# Operant-Front.net
KiCad netlist of a schematic drawn in EAGLE
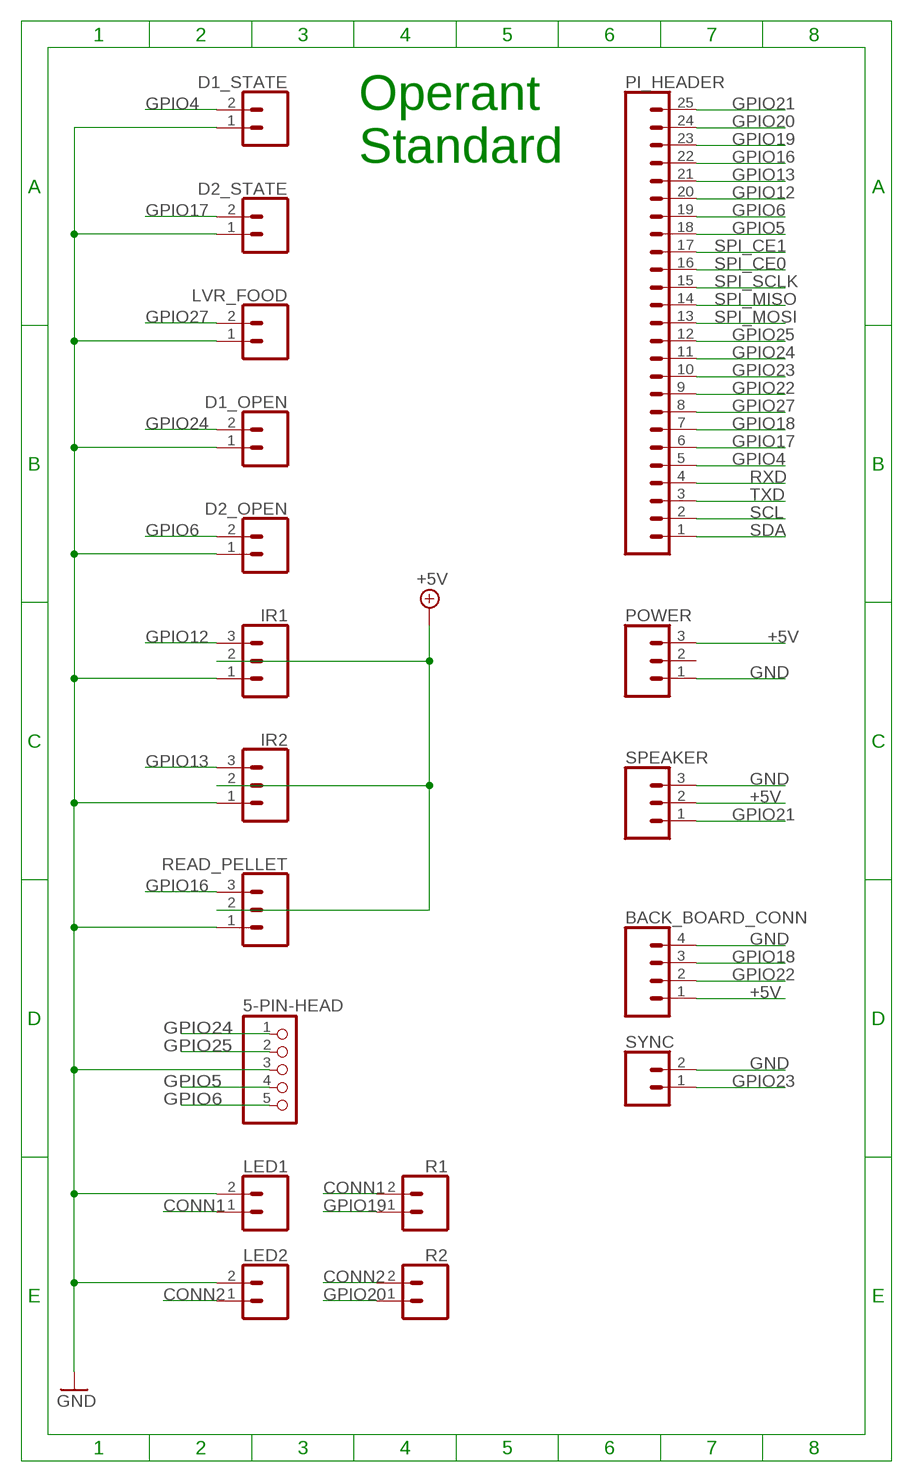
[diagram p0: schematic, sheet 1]

(export (version "E")
  (design (tool "Eeschema 10.0.6"))
  (components
    (comp (ref "5-PIN-HEAD")
      (value "PINHD-1X5")
      (footprint "eagle-import:1X05")
      (libsource (lib "eagle-import") (part "PINHD-1X5"))
    )
    (comp (ref "BACK_BOARD_CONN")
      (value "CONN_04JST-PTH")
      (footprint "eagle-import:JST-4-PTH")
      (libsource (lib "eagle-import") (part "CONN_04JST-PTH"))
    )
    (comp (ref "D1_OPEN")
      (value "CONN_02JST-PTH-2")
      (footprint "eagle-import:JST-2-PTH")
      (libsource (lib "eagle-import") (part "CONN_02JST-PTH-2"))
    )
    (comp (ref "D1_STATE")
      (value "CONN_02JST-PTH-2")
      (footprint "eagle-import:JST-2-PTH")
      (libsource (lib "eagle-import") (part "CONN_02JST-PTH-2"))
    )
    (comp (ref "D2_OPEN")
      (value "CONN_02JST-PTH-2")
      (footprint "eagle-import:JST-2-PTH")
      (libsource (lib "eagle-import") (part "CONN_02JST-PTH-2"))
    )
    (comp (ref "D2_STATE")
      (value "CONN_02JST-PTH-2")
      (footprint "eagle-import:JST-2-PTH")
      (libsource (lib "eagle-import") (part "CONN_02JST-PTH-2"))
    )
    (comp (ref "IR1")
      (value "CONN_03JST-PTH")
      (footprint "eagle-import:JST-3-PTH")
      (libsource (lib "eagle-import") (part "CONN_03JST-PTH"))
    )
    (comp (ref "IR2")
      (value "CONN_03JST-PTH")
      (footprint "eagle-import:JST-3-PTH")
      (libsource (lib "eagle-import") (part "CONN_03JST-PTH"))
    )
    (comp (ref "LED1")
      (value "CONN_02")
      (footprint "eagle-import:1X02")
      (libsource (lib "eagle-import") (part "CONN_02"))
    )
    (comp (ref "LED2")
      (value "CONN_02")
      (footprint "eagle-import:1X02")
      (libsource (lib "eagle-import") (part "CONN_02"))
    )
    (comp (ref "LVR_FOOD")
      (value "CONN_02JST-PTH-2")
      (footprint "eagle-import:JST-2-PTH")
      (libsource (lib "eagle-import") (part "CONN_02JST-PTH-2"))
    )
    (comp (ref "PI_HEADER")
      (value "CONN_25")
      (footprint "eagle-import:1X25")
      (libsource (lib "eagle-import") (part "CONN_25"))
    )
    (comp (ref "POWER")
      (value "CONN_03")
      (footprint "eagle-import:1X03")
      (libsource (lib "eagle-import") (part "CONN_03"))
    )
    (comp (ref "R1")
      (value "CONN_02")
      (footprint "eagle-import:1X02")
      (libsource (lib "eagle-import") (part "CONN_02"))
    )
    (comp (ref "R2")
      (value "CONN_02")
      (footprint "eagle-import:1X02")
      (libsource (lib "eagle-import") (part "CONN_02"))
    )
    (comp (ref "READ_PELLET")
      (value "CONN_03JST-PTH")
      (footprint "eagle-import:JST-3-PTH")
      (libsource (lib "eagle-import") (part "CONN_03JST-PTH"))
    )
    (comp (ref "SPEAKER")
      (value "CONN_03JST-PTH")
      (footprint "eagle-import:JST-3-PTH")
      (libsource (lib "eagle-import") (part "CONN_03JST-PTH"))
    )
    (comp (ref "SYNC")
      (value "CONN_02")
      (footprint "eagle-import:1X02")
      (libsource (lib "eagle-import") (part "CONN_02"))
    )
  )
  (nets
    (net (code "1") (name "+5V") (class "Default")
      (node (ref "BACK_BOARD_CONN") (pin "1") (pinfunction "1_1") (pintype "passive"))
      (node (ref "IR1") (pin "2") (pinfunction "2_2") (pintype "passive"))
      (node (ref "IR2") (pin "2") (pinfunction "2_2") (pintype "passive"))
      (node (ref "POWER") (pin "3") (pinfunction "3_3") (pintype "passive"))
      (node (ref "READ_PELLET") (pin "2") (pinfunction "2_2") (pintype "passive"))
      (node (ref "SPEAKER") (pin "2") (pinfunction "2_2") (pintype "passive"))
    )
    (net (code "2") (name "/CONN1") (class "Default")
      (node (ref "LED1") (pin "1") (pinfunction "1_1") (pintype "passive"))
      (node (ref "R1") (pin "2") (pinfunction "2_2") (pintype "passive"))
    )
    (net (code "3") (name "/CONN2") (class "Default")
      (node (ref "LED2") (pin "1") (pinfunction "1_1") (pintype "passive"))
      (node (ref "R2") (pin "2") (pinfunction "2_2") (pintype "passive"))
    )
    (net (code "4") (name "/GPIO4") (class "Default")
      (node (ref "D1_STATE") (pin "2") (pinfunction "2_2") (pintype "passive"))
      (node (ref "PI_HEADER") (pin "5") (pinfunction "5_5") (pintype "passive"))
    )
    (net (code "5") (name "/GPIO5") (class "Default")
      (node (ref "5-PIN-HEAD") (pin "4") (pinfunction "4_4") (pintype "passive"))
      (node (ref "PI_HEADER") (pin "18") (pinfunction "18_18") (pintype "passive"))
    )
    (net (code "6") (name "/GPIO6") (class "Default")
      (node (ref "5-PIN-HEAD") (pin "5") (pinfunction "5_5") (pintype "passive"))
      (node (ref "D2_OPEN") (pin "2") (pinfunction "2_2") (pintype "passive"))
      (node (ref "PI_HEADER") (pin "19") (pinfunction "19_19") (pintype "passive"))
    )
    (net (code "7") (name "/GPIO12") (class "Default")
      (node (ref "IR1") (pin "3") (pinfunction "3_3") (pintype "passive"))
      (node (ref "PI_HEADER") (pin "20") (pinfunction "20_20") (pintype "passive"))
    )
    (net (code "8") (name "/GPIO13") (class "Default")
      (node (ref "IR2") (pin "3") (pinfunction "3_3") (pintype "passive"))
      (node (ref "PI_HEADER") (pin "21") (pinfunction "21_21") (pintype "passive"))
    )
    (net (code "9") (name "/GPIO16") (class "Default")
      (node (ref "PI_HEADER") (pin "22") (pinfunction "22_22") (pintype "passive"))
      (node (ref "READ_PELLET") (pin "3") (pinfunction "3_3") (pintype "passive"))
    )
    (net (code "10") (name "/GPIO17") (class "Default")
      (node (ref "D2_STATE") (pin "2") (pinfunction "2_2") (pintype "passive"))
      (node (ref "PI_HEADER") (pin "6") (pinfunction "6_6") (pintype "passive"))
    )
    (net (code "11") (name "/GPIO18") (class "Default")
      (node (ref "BACK_BOARD_CONN") (pin "3") (pinfunction "3_3") (pintype "passive"))
      (node (ref "PI_HEADER") (pin "7") (pinfunction "7_7") (pintype "passive"))
    )
    (net (code "12") (name "/GPIO19") (class "Default")
      (node (ref "PI_HEADER") (pin "23") (pinfunction "23_23") (pintype "passive"))
      (node (ref "R1") (pin "1") (pinfunction "1_1") (pintype "passive"))
    )
    (net (code "13") (name "/GPIO20") (class "Default")
      (node (ref "PI_HEADER") (pin "24") (pinfunction "24_24") (pintype "passive"))
      (node (ref "R2") (pin "1") (pinfunction "1_1") (pintype "passive"))
    )
    (net (code "14") (name "/GPIO21") (class "Default")
      (node (ref "PI_HEADER") (pin "25") (pinfunction "25_25") (pintype "passive"))
      (node (ref "SPEAKER") (pin "1") (pinfunction "1_1") (pintype "passive"))
    )
    (net (code "15") (name "/GPIO22") (class "Default")
      (node (ref "BACK_BOARD_CONN") (pin "2") (pinfunction "2_2") (pintype "passive"))
      (node (ref "PI_HEADER") (pin "9") (pinfunction "9_9") (pintype "passive"))
    )
    (net (code "16") (name "/GPIO23") (class "Default")
      (node (ref "PI_HEADER") (pin "10") (pinfunction "10_10") (pintype "passive"))
      (node (ref "SYNC") (pin "1") (pinfunction "1_1") (pintype "passive"))
    )
    (net (code "17") (name "/GPIO24") (class "Default")
      (node (ref "5-PIN-HEAD") (pin "1") (pinfunction "1_1") (pintype "passive"))
      (node (ref "D1_OPEN") (pin "2") (pinfunction "2_2") (pintype "passive"))
      (node (ref "PI_HEADER") (pin "11") (pinfunction "11_11") (pintype "passive"))
    )
    (net (code "18") (name "/GPIO25") (class "Default")
      (node (ref "5-PIN-HEAD") (pin "2") (pinfunction "2_2") (pintype "passive"))
      (node (ref "PI_HEADER") (pin "12") (pinfunction "12_12") (pintype "passive"))
    )
    (net (code "19") (name "/GPIO27") (class "Default")
      (node (ref "LVR_FOOD") (pin "2") (pinfunction "2_2") (pintype "passive"))
      (node (ref "PI_HEADER") (pin "8") (pinfunction "8_8") (pintype "passive"))
    )
    (net (code "20") (name "/RXD") (class "Default")
      (node (ref "PI_HEADER") (pin "4") (pinfunction "4_4") (pintype "passive"))
    )
    (net (code "21") (name "/SCL") (class "Default")
      (node (ref "PI_HEADER") (pin "2") (pinfunction "2_2") (pintype "passive"))
    )
    (net (code "22") (name "/SDA") (class "Default")
      (node (ref "PI_HEADER") (pin "1") (pinfunction "1_1") (pintype "passive"))
    )
    (net (code "23") (name "/SPI_CE0") (class "Default")
      (node (ref "PI_HEADER") (pin "16") (pinfunction "16_16") (pintype "passive"))
    )
    (net (code "24") (name "/SPI_CE1") (class "Default")
      (node (ref "PI_HEADER") (pin "17") (pinfunction "17_17") (pintype "passive"))
    )
    (net (code "25") (name "/SPI_MISO") (class "Default")
      (node (ref "PI_HEADER") (pin "14") (pinfunction "14_14") (pintype "passive"))
    )
    (net (code "26") (name "/SPI_MOSI") (class "Default")
      (node (ref "PI_HEADER") (pin "13") (pinfunction "13_13") (pintype "passive"))
    )
    (net (code "27") (name "/SPI_SCLK") (class "Default")
      (node (ref "PI_HEADER") (pin "15") (pinfunction "15_15") (pintype "passive"))
    )
    (net (code "28") (name "/TXD") (class "Default")
      (node (ref "PI_HEADER") (pin "3") (pinfunction "3_3") (pintype "passive"))
    )
    (net (code "29") (name "GND") (class "Default")
      (node (ref "5-PIN-HEAD") (pin "3") (pinfunction "3_3") (pintype "passive"))
      (node (ref "BACK_BOARD_CONN") (pin "4") (pinfunction "4_4") (pintype "passive"))
      (node (ref "D1_OPEN") (pin "1") (pinfunction "1_1") (pintype "passive"))
      (node (ref "D1_STATE") (pin "1") (pinfunction "1_1") (pintype "passive"))
      (node (ref "D2_OPEN") (pin "1") (pinfunction "1_1") (pintype "passive"))
      (node (ref "D2_STATE") (pin "1") (pinfunction "1_1") (pintype "passive"))
      (node (ref "IR1") (pin "1") (pinfunction "1_1") (pintype "passive"))
      (node (ref "IR2") (pin "1") (pinfunction "1_1") (pintype "passive"))
      (node (ref "LED1") (pin "2") (pinfunction "2_2") (pintype "passive"))
      (node (ref "LED2") (pin "2") (pinfunction "2_2") (pintype "passive"))
      (node (ref "LVR_FOOD") (pin "1") (pinfunction "1_1") (pintype "passive"))
      (node (ref "POWER") (pin "1") (pinfunction "1_1") (pintype "passive"))
      (node (ref "READ_PELLET") (pin "1") (pinfunction "1_1") (pintype "passive"))
      (node (ref "SPEAKER") (pin "3") (pinfunction "3_3") (pintype "passive"))
      (node (ref "SYNC") (pin "2") (pinfunction "2_2") (pintype "passive"))
    )
    (net (code "30") (name "unconnected-(POWER-Pad2)") (class "Default")
      (node (ref "POWER") (pin "2") (pinfunction "2_2") (pintype "passive"))
    )
  )
)
